# svd.net
KiCad netlist of a schematic drawn in EAGLE
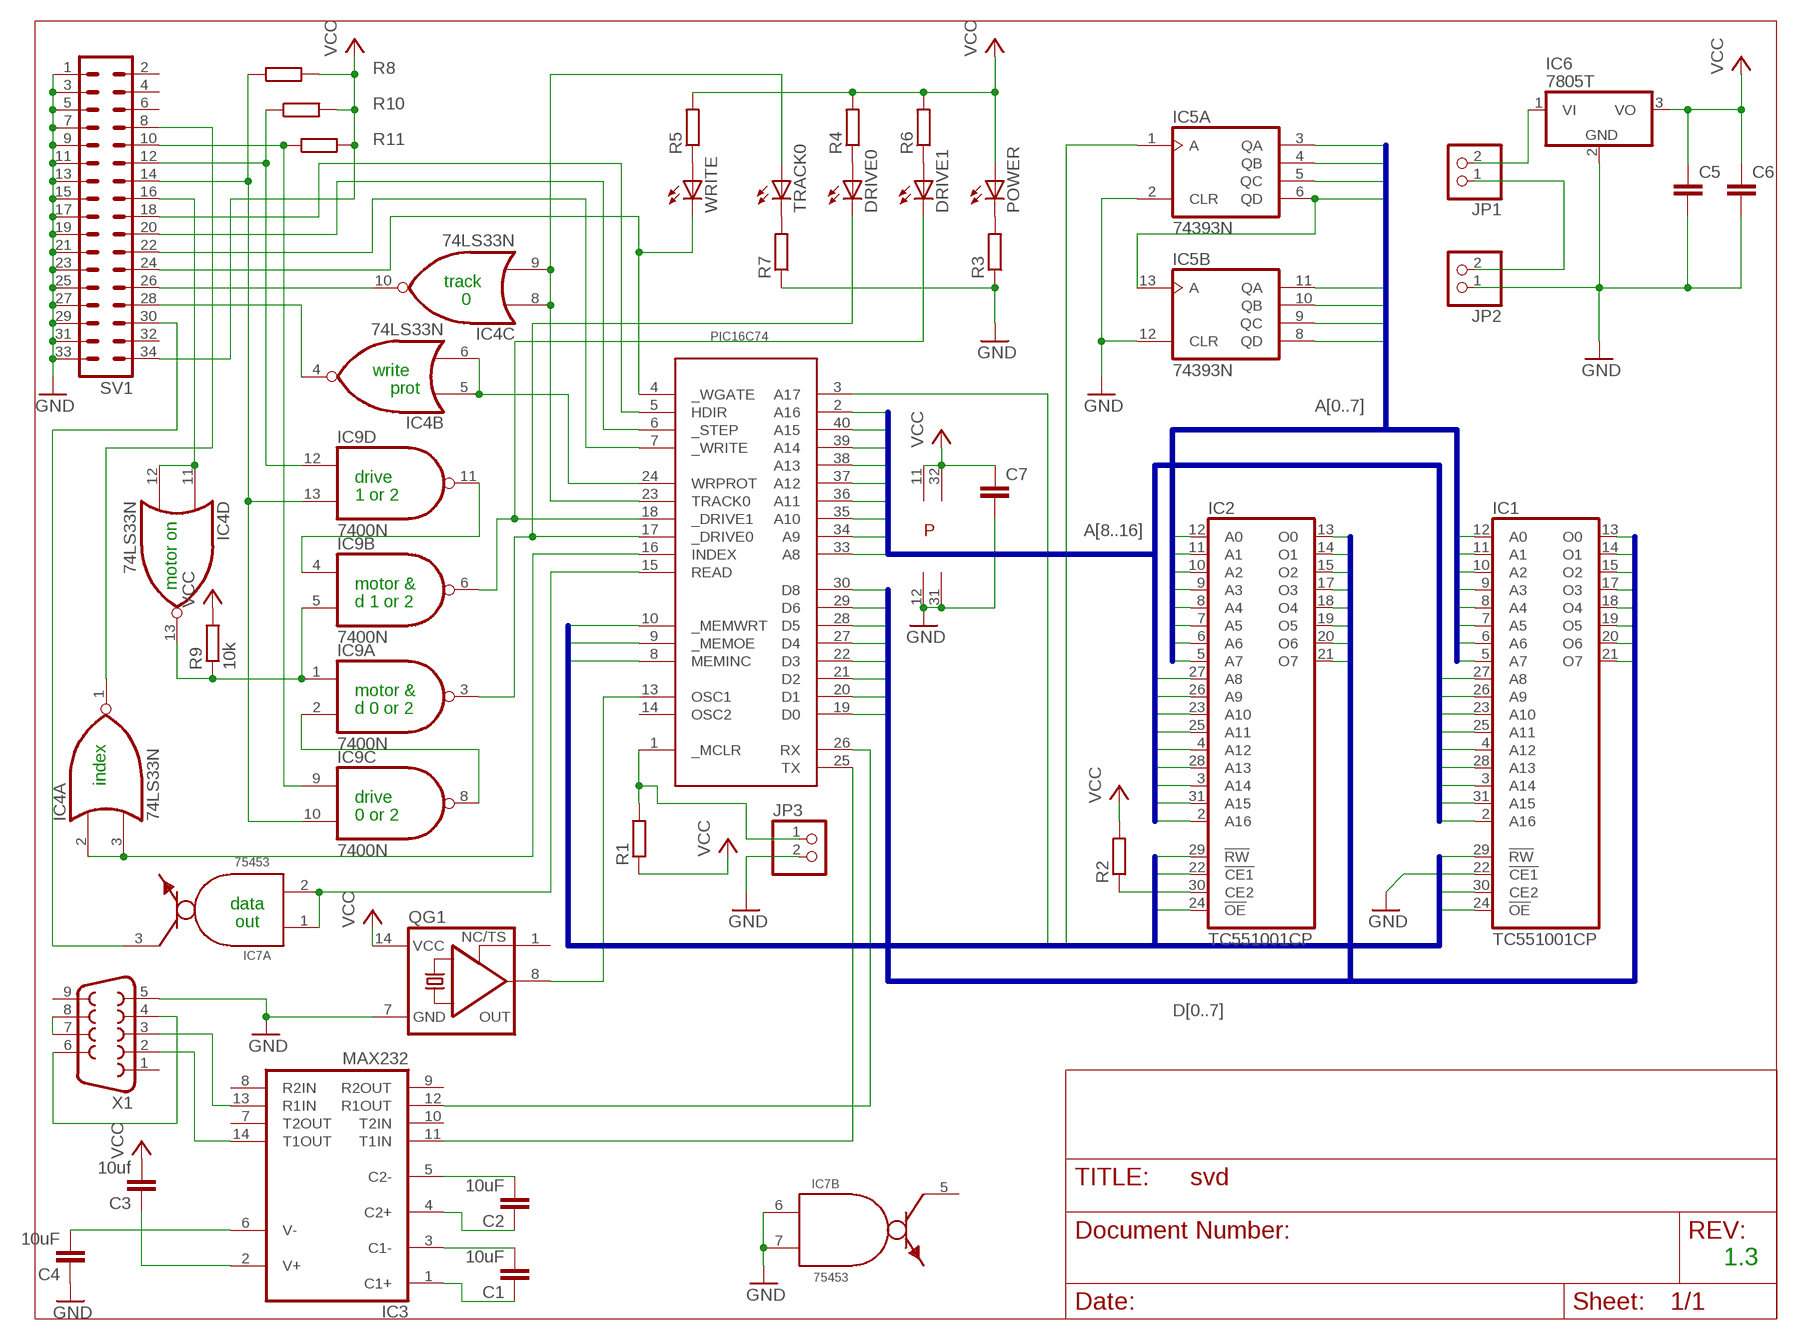
[diagram p0: schematic, sheet 1]

(export (version "E")
  (design (tool "Eeschema 10.0.6"))
  (components
    (comp (ref "C1")
      (value "10uF")
      (footprint "eagle-import:C2.5-5")
      (libsource (lib "eagle-import") (part "C2.5/5"))
    )
    (comp (ref "C2")
      (value "10uF")
      (footprint "eagle-import:C2.5-5")
      (libsource (lib "eagle-import") (part "C2.5/5"))
    )
    (comp (ref "C3")
      (value "10uf")
      (footprint "eagle-import:C2.5-5")
      (libsource (lib "eagle-import") (part "C2.5/5"))
    )
    (comp (ref "C4")
      (value "10uF")
      (footprint "eagle-import:C2.5-5")
      (libsource (lib "eagle-import") (part "C2.5/5"))
    )
    (comp (ref "C5")
      (value "C5/5")
      (footprint "eagle-import:C5B5")
      (libsource (lib "eagle-import") (part "C5/5"))
    )
    (comp (ref "C6")
      (value "C5/5")
      (footprint "eagle-import:C5B5")
      (libsource (lib "eagle-import") (part "C5/5"))
    )
    (comp (ref "C7")
      (value "C2,5-3")
      (footprint "eagle-import:C2.5-3")
      (libsource (lib "eagle-import") (part "C2,5-3"))
    )
    (comp (ref "DRIVE0")
      (value "LED3MM")
      (footprint "eagle-import:LED3MM")
      (libsource (lib "eagle-import") (part "LED3MM"))
    )
    (comp (ref "DRIVE1")
      (value "LED3MM")
      (footprint "eagle-import:LED3MM")
      (libsource (lib "eagle-import") (part "LED3MM"))
    )
    (comp (ref "IC1")
      (value "TC551001CP")
      (footprint "eagle-import:DIL32")
      (libsource (lib "eagle-import") (part "TC551001CP"))
    )
    (comp (ref "IC2")
      (value "TC551001CP")
      (footprint "eagle-import:DIL32")
      (libsource (lib "eagle-import") (part "TC551001CP"))
    )
    (comp (ref "IC3")
      (value "MAX232")
      (footprint "eagle-import:DIL16")
      (fields (field (name "MF") "MAXIM") (field (name "MPN") "MAX232ACPE+"))
      (libsource (lib "eagle-import") (part "MAX232"))
    )
    (comp (ref "IC4")
      (value "74LS33N")
      (footprint "eagle-import:DIL14")
      (libsource (lib "eagle-import") (part "7433NLS"))
    )
    (comp (ref "IC5")
      (value "74393N")
      (footprint "eagle-import:DIL14")
      (libsource (lib "eagle-import") (part "74393N"))
    )
    (comp (ref "IC6")
      (value "7805T")
      (footprint "eagle-import:TO220H")
      (libsource (lib "eagle-import") (part "78T05"))
    )
    (comp (ref "IC7")
      (value "75453")
      (footprint "eagle-import:DIL08")
      (libsource (lib "eagle-import") (part "75453"))
    )
    (comp (ref "IC9")
      (value "7400N")
      (footprint "eagle-import:DIL14")
      (libsource (lib "eagle-import") (part "7400N"))
    )
    (comp (ref "JP1")
      (value "PINHD-1X2")
      (footprint "eagle-import:1X02")
      (libsource (lib "eagle-import") (part "PINHD-1X2"))
    )
    (comp (ref "JP2")
      (value "PINHD-1X2")
      (footprint "eagle-import:1X02")
      (libsource (lib "eagle-import") (part "PINHD-1X2"))
    )
    (comp (ref "JP3")
      (value "PINHD-1X2")
      (footprint "eagle-import:1X02")
      (libsource (lib "eagle-import") (part "PINHD-1X2"))
    )
    (comp (ref "PIC16C74")
      (value "SVD-PIC16C74")
      (footprint "eagle-import:DIL40")
      (libsource (lib "eagle-import") (part "SVD-PIC16C74"))
    )
    (comp (ref "POWER")
      (value "LED3MM")
      (footprint "eagle-import:LED3MM")
      (libsource (lib "eagle-import") (part "LED3MM"))
    )
    (comp (ref "QG1")
      (value "XO-14")
      (footprint "eagle-import:DIL14S")
      (libsource (lib "eagle-import") (part "XO-14"))
    )
    (comp (ref "R1")
      (value "R-EU_0204/5")
      (footprint "eagle-import:0204_5")
      (libsource (lib "eagle-import") (part "R-EU_0204/5"))
    )
    (comp (ref "R2")
      (value "R-EU_0204/5")
      (footprint "eagle-import:0204_5")
      (libsource (lib "eagle-import") (part "R-EU_0204/5"))
    )
    (comp (ref "R3")
      (value "R-EU_0204/5")
      (footprint "eagle-import:0204_5")
      (libsource (lib "eagle-import") (part "R-EU_0204/5"))
    )
    (comp (ref "R4")
      (value "R-EU_0204/5")
      (footprint "eagle-import:0204_5")
      (libsource (lib "eagle-import") (part "R-EU_0204/5"))
    )
    (comp (ref "R5")
      (value "R-EU_0204/5")
      (footprint "eagle-import:0204_5")
      (libsource (lib "eagle-import") (part "R-EU_0204/5"))
    )
    (comp (ref "R6")
      (value "R-EU_0204/5")
      (footprint "eagle-import:0204_5")
      (libsource (lib "eagle-import") (part "R-EU_0204/5"))
    )
    (comp (ref "R7")
      (value "R-EU_0204/5")
      (footprint "eagle-import:0204_5")
      (libsource (lib "eagle-import") (part "R-EU_0204/5"))
    )
    (comp (ref "R8")
      (value "R-EU_0204/5")
      (footprint "eagle-import:0204_5")
      (libsource (lib "eagle-import") (part "R-EU_0204/5"))
    )
    (comp (ref "R9")
      (value "10k")
      (footprint "eagle-import:0204_5")
      (libsource (lib "eagle-import") (part "R-EU_0204/5"))
    )
    (comp (ref "R10")
      (value "R-EU_0204/5")
      (footprint "eagle-import:0204_5")
      (libsource (lib "eagle-import") (part "R-EU_0204/5"))
    )
    (comp (ref "R11")
      (value "R-EU_0204/5")
      (footprint "eagle-import:0204_5")
      (libsource (lib "eagle-import") (part "R-EU_0204/5"))
    )
    (comp (ref "SV1")
      (value "ML34")
      (footprint "eagle-import:ML34")
      (libsource (lib "eagle-import") (part "ML34"))
    )
    (comp (ref "TRACK0")
      (value "LED3MM")
      (footprint "eagle-import:LED3MM")
      (libsource (lib "eagle-import") (part "LED3MM"))
    )
    (comp (ref "WRITE")
      (value "LED3MM")
      (footprint "eagle-import:LED3MM")
      (libsource (lib "eagle-import") (part "LED3MM"))
    )
    (comp (ref "X1")
      (value "F09HP")
      (footprint "eagle-import:F09HP")
      (libsource (lib "eagle-import") (part "F09HP"))
    )
  )
  (nets
    (net (code "1") (name "/A0") (class "Default")
      (node (ref "IC1") (pin "12") (pinfunction "A0_12") (pintype "input"))
      (node (ref "IC2") (pin "12") (pinfunction "A0_12") (pintype "input"))
      (node (ref "IC5") (pin "3") (pinfunction "QA_3") (pintype "output"))
    )
    (net (code "2") (name "/A1") (class "Default")
      (node (ref "IC1") (pin "11") (pinfunction "A1_11") (pintype "input"))
      (node (ref "IC2") (pin "11") (pinfunction "A1_11") (pintype "input"))
      (node (ref "IC5") (pin "4") (pinfunction "QB_4") (pintype "output"))
    )
    (net (code "3") (name "/A2") (class "Default")
      (node (ref "IC1") (pin "10") (pinfunction "A2_10") (pintype "input"))
      (node (ref "IC2") (pin "10") (pinfunction "A2_10") (pintype "input"))
      (node (ref "IC5") (pin "5") (pinfunction "QC_5") (pintype "output"))
    )
    (net (code "4") (name "/A3") (class "Default")
      (node (ref "IC1") (pin "9") (pinfunction "A3_9") (pintype "input"))
      (node (ref "IC2") (pin "9") (pinfunction "A3_9") (pintype "input"))
      (node (ref "IC5") (pin "13") (pinfunction "A_13") (pintype "input"))
      (node (ref "IC5") (pin "6") (pinfunction "QD_6") (pintype "output"))
    )
    (net (code "5") (name "/A4") (class "Default")
      (node (ref "IC1") (pin "8") (pinfunction "A4_8") (pintype "input"))
      (node (ref "IC2") (pin "8") (pinfunction "A4_8") (pintype "input"))
      (node (ref "IC5") (pin "11") (pinfunction "QA_11") (pintype "output"))
    )
    (net (code "6") (name "/A5") (class "Default")
      (node (ref "IC1") (pin "7") (pinfunction "A5_7") (pintype "input"))
      (node (ref "IC2") (pin "7") (pinfunction "A5_7") (pintype "input"))
      (node (ref "IC5") (pin "10") (pinfunction "QB_10") (pintype "output"))
    )
    (net (code "7") (name "/A6") (class "Default")
      (node (ref "IC1") (pin "6") (pinfunction "A6_6") (pintype "input"))
      (node (ref "IC2") (pin "6") (pinfunction "A6_6") (pintype "input"))
      (node (ref "IC5") (pin "9") (pinfunction "QC_9") (pintype "output"))
    )
    (net (code "8") (name "/A7") (class "Default")
      (node (ref "IC1") (pin "5") (pinfunction "A7_5") (pintype "input"))
      (node (ref "IC2") (pin "5") (pinfunction "A7_5") (pintype "input"))
      (node (ref "IC5") (pin "8") (pinfunction "QD_8") (pintype "output"))
    )
    (net (code "9") (name "/A8") (class "Default")
      (node (ref "IC1") (pin "27") (pinfunction "A8_27") (pintype "input"))
      (node (ref "IC2") (pin "27") (pinfunction "A8_27") (pintype "input"))
      (node (ref "PIC16C74") (pin "33") (pinfunction "A8_33") (pintype "output"))
    )
    (net (code "10") (name "/A9") (class "Default")
      (node (ref "IC1") (pin "26") (pinfunction "A9_26") (pintype "input"))
      (node (ref "IC2") (pin "26") (pinfunction "A9_26") (pintype "input"))
      (node (ref "PIC16C74") (pin "34") (pinfunction "A9_34") (pintype "output"))
    )
    (net (code "11") (name "/A10") (class "Default")
      (node (ref "IC1") (pin "23") (pinfunction "A10_23") (pintype "input"))
      (node (ref "IC2") (pin "23") (pinfunction "A10_23") (pintype "input"))
      (node (ref "PIC16C74") (pin "35") (pinfunction "A10_35") (pintype "output"))
    )
    (net (code "12") (name "/A11") (class "Default")
      (node (ref "IC1") (pin "25") (pinfunction "A11_25") (pintype "input"))
      (node (ref "IC2") (pin "25") (pinfunction "A11_25") (pintype "input"))
      (node (ref "PIC16C74") (pin "36") (pinfunction "A11_36") (pintype "output"))
    )
    (net (code "13") (name "/A12") (class "Default")
      (node (ref "IC1") (pin "4") (pinfunction "A12_4") (pintype "input"))
      (node (ref "IC2") (pin "4") (pinfunction "A12_4") (pintype "input"))
      (node (ref "PIC16C74") (pin "37") (pinfunction "A12_37") (pintype "output"))
    )
    (net (code "14") (name "/A13") (class "Default")
      (node (ref "IC1") (pin "28") (pinfunction "A13_28") (pintype "input"))
      (node (ref "IC2") (pin "28") (pinfunction "A13_28") (pintype "input"))
      (node (ref "PIC16C74") (pin "38") (pinfunction "A13_38") (pintype "output"))
    )
    (net (code "15") (name "/A14") (class "Default")
      (node (ref "IC1") (pin "3") (pinfunction "A14_3") (pintype "input"))
      (node (ref "IC2") (pin "3") (pinfunction "A14_3") (pintype "input"))
      (node (ref "PIC16C74") (pin "39") (pinfunction "A14_39") (pintype "output"))
    )
    (net (code "16") (name "/A15") (class "Default")
      (node (ref "IC1") (pin "31") (pinfunction "A15_31") (pintype "input"))
      (node (ref "IC2") (pin "31") (pinfunction "A15_31") (pintype "input"))
      (node (ref "PIC16C74") (pin "40") (pinfunction "A15_40") (pintype "output"))
    )
    (net (code "17") (name "/A16") (class "Default")
      (node (ref "IC1") (pin "2") (pinfunction "A16_2") (pintype "input"))
      (node (ref "IC2") (pin "2") (pinfunction "A16_2") (pintype "input"))
      (node (ref "PIC16C74") (pin "2") (pinfunction "A16_2") (pintype "output"))
    )
    (net (code "18") (name "/A17") (class "Default")
      (node (ref "IC1") (pin "30") (pinfunction "CE2_30") (pintype "input"))
      (node (ref "IC2") (pin "22") (pinfunction "~{CE1}_22") (pintype "input"))
      (node (ref "PIC16C74") (pin "3") (pinfunction "A17_3") (pintype "output"))
    )
    (net (code "21") (name "/CLK") (class "Default")
      (node (ref "IC5") (pin "1") (pinfunction "A_1") (pintype "input"))
      (node (ref "PIC16C74") (pin "8") (pinfunction "MEMINC_8") (pintype "output"))
    )
    (net (code "22") (name "/D0") (class "Default")
      (node (ref "IC1") (pin "13") (pinfunction "O0_13") (pintype "tri_state"))
      (node (ref "IC2") (pin "13") (pinfunction "O0_13") (pintype "tri_state"))
      (node (ref "PIC16C74") (pin "19") (pinfunction "D0_19") (pintype "bidirectional"))
    )
    (net (code "23") (name "/D1") (class "Default")
      (node (ref "IC1") (pin "14") (pinfunction "O1_14") (pintype "tri_state"))
      (node (ref "IC2") (pin "14") (pinfunction "O1_14") (pintype "tri_state"))
      (node (ref "PIC16C74") (pin "20") (pinfunction "D1_20") (pintype "bidirectional"))
    )
    (net (code "24") (name "/D2") (class "Default")
      (node (ref "IC1") (pin "15") (pinfunction "O2_15") (pintype "tri_state"))
      (node (ref "IC2") (pin "15") (pinfunction "O2_15") (pintype "tri_state"))
      (node (ref "PIC16C74") (pin "21") (pinfunction "D2_21") (pintype "bidirectional"))
    )
    (net (code "25") (name "/D3") (class "Default")
      (node (ref "IC1") (pin "17") (pinfunction "O3_17") (pintype "tri_state"))
      (node (ref "IC2") (pin "17") (pinfunction "O3_17") (pintype "tri_state"))
      (node (ref "PIC16C74") (pin "22") (pinfunction "D3_22") (pintype "bidirectional"))
    )
    (net (code "26") (name "/D4") (class "Default")
      (node (ref "IC1") (pin "18") (pinfunction "O4_18") (pintype "tri_state"))
      (node (ref "IC2") (pin "18") (pinfunction "O4_18") (pintype "tri_state"))
      (node (ref "PIC16C74") (pin "27") (pinfunction "D4_27") (pintype "bidirectional"))
    )
    (net (code "27") (name "/D5") (class "Default")
      (node (ref "IC1") (pin "19") (pinfunction "O5_19") (pintype "tri_state"))
      (node (ref "IC2") (pin "19") (pinfunction "O5_19") (pintype "tri_state"))
      (node (ref "PIC16C74") (pin "28") (pinfunction "D5_28") (pintype "bidirectional"))
    )
    (net (code "28") (name "/D6") (class "Default")
      (node (ref "IC1") (pin "20") (pinfunction "O6_20") (pintype "tri_state"))
      (node (ref "IC2") (pin "20") (pinfunction "O6_20") (pintype "tri_state"))
      (node (ref "PIC16C74") (pin "29") (pinfunction "D6_29") (pintype "bidirectional"))
    )
    (net (code "29") (name "/D7") (class "Default")
      (node (ref "IC1") (pin "21") (pinfunction "O7_21") (pintype "tri_state"))
      (node (ref "IC2") (pin "21") (pinfunction "O7_21") (pintype "tri_state"))
      (node (ref "PIC16C74") (pin "30") (pinfunction "D8_30") (pintype "bidirectional"))
    )
    (net (code "31") (name "/~{OE}") (class "Default")
      (node (ref "IC1") (pin "24") (pinfunction "~{OE}_24") (pintype "input"))
      (node (ref "IC2") (pin "24") (pinfunction "~{OE}_24") (pintype "input"))
      (node (ref "PIC16C74") (pin "9") (pinfunction "_MEMOE_9") (pintype "output"))
    )
    (net (code "32") (name "/~{WE}") (class "Default")
      (node (ref "IC1") (pin "29") (pinfunction "~{RW}_29") (pintype "input"))
      (node (ref "IC2") (pin "29") (pinfunction "~{RW}_29") (pintype "input"))
      (node (ref "PIC16C74") (pin "10") (pinfunction "_MEMWRT_10") (pintype "output"))
    )
    (net (code "33") (name "GND") (class "Default")
      (node (ref "C4") (pin "1") (pinfunction "1_1") (pintype "passive"))
      (node (ref "C5") (pin "2") (pinfunction "2_2") (pintype "passive"))
      (node (ref "C6") (pin "2") (pinfunction "2_2") (pintype "passive"))
      (node (ref "C7") (pin "2") (pinfunction "2_2") (pintype "passive"))
      (node (ref "IC1") (pin "22") (pinfunction "~{CE1}_22") (pintype "input"))
      (node (ref "IC5") (pin "12") (pinfunction "CLR_12") (pintype "input"))
      (node (ref "IC5") (pin "2") (pinfunction "CLR_2") (pintype "input"))
      (node (ref "IC6") (pin "2") (pinfunction "GND_2") (pintype "passive"))
      (node (ref "IC7") (pin "6") (pinfunction "I0_6") (pintype "input"))
      (node (ref "IC7") (pin "7") (pinfunction "I1_7") (pintype "input"))
      (node (ref "JP2") (pin "1") (pinfunction "1_1") (pintype "passive"))
      (node (ref "JP3") (pin "2") (pinfunction "2_2") (pintype "passive"))
      (node (ref "PIC16C74") (pin "12") (pinfunction "GND_12") (pintype "power_in"))
      (node (ref "PIC16C74") (pin "31") (pinfunction "GND_31") (pintype "power_in"))
      (node (ref "QG1") (pin "7") (pinfunction "GND_7") (pintype "power_in"))
      (node (ref "R3") (pin "1") (pinfunction "1_1") (pintype "passive"))
      (node (ref "R7") (pin "1") (pinfunction "1_1") (pintype "passive"))
      (node (ref "SV1") (pin "1") (pinfunction "1_1") (pintype "passive"))
      (node (ref "SV1") (pin "11") (pinfunction "11_11") (pintype "passive"))
      (node (ref "SV1") (pin "13") (pinfunction "13_13") (pintype "passive"))
      (node (ref "SV1") (pin "15") (pinfunction "15_15") (pintype "passive"))
      (node (ref "SV1") (pin "17") (pinfunction "17_17") (pintype "passive"))
      (node (ref "SV1") (pin "19") (pinfunction "19_19") (pintype "passive"))
      (node (ref "SV1") (pin "21") (pinfunction "21_21") (pintype "passive"))
      (node (ref "SV1") (pin "23") (pinfunction "23_23") (pintype "passive"))
      (node (ref "SV1") (pin "25") (pinfunction "25_25") (pintype "passive"))
      (node (ref "SV1") (pin "27") (pinfunction "27_27") (pintype "passive"))
      (node (ref "SV1") (pin "29") (pinfunction "29_29") (pintype "passive"))
      (node (ref "SV1") (pin "3") (pinfunction "3_3") (pintype "passive"))
      (node (ref "SV1") (pin "31") (pinfunction "31_31") (pintype "passive"))
      (node (ref "SV1") (pin "33") (pinfunction "33_33") (pintype "passive"))
      (node (ref "SV1") (pin "5") (pinfunction "5_5") (pintype "passive"))
      (node (ref "SV1") (pin "7") (pinfunction "7_7") (pintype "passive"))
      (node (ref "SV1") (pin "9") (pinfunction "9_9") (pintype "passive"))
      (node (ref "X1") (pin "5") (pinfunction "5_5") (pintype "passive"))
    )
    (net (code "34") (name "Net-(DRIVE0-C)") (class "Default")
      (node (ref "DRIVE0") (pin "K") (pinfunction "C_K") (pintype "passive"))
      (node (ref "IC9") (pin "3") (pinfunction "O_3") (pintype "output"))
      (node (ref "PIC16C74") (pin "17") (pinfunction "_DRIVE0_17") (pintype "input"))
    )
    (net (code "35") (name "Net-(DRIVE0-PadA)") (class "Default")
      (node (ref "DRIVE0") (pin "A") (pinfunction "A_A") (pintype "passive"))
      (node (ref "R4") (pin "1") (pinfunction "1_1") (pintype "passive"))
    )
    (net (code "36") (name "Net-(DRIVE1-C)") (class "Default")
      (node (ref "DRIVE1") (pin "K") (pinfunction "C_K") (pintype "passive"))
      (node (ref "IC9") (pin "6") (pinfunction "O_6") (pintype "output"))
      (node (ref "PIC16C74") (pin "18") (pinfunction "_DRIVE1_18") (pintype "input"))
    )
    (net (code "37") (name "Net-(DRIVE1-PadA)") (class "Default")
      (node (ref "DRIVE1") (pin "A") (pinfunction "A_A") (pintype "passive"))
      (node (ref "R6") (pin "1") (pinfunction "1_1") (pintype "passive"))
    )
    (net (code "38") (name "Net-(IC2B-CE2)") (class "Default")
      (node (ref "IC2") (pin "30") (pinfunction "CE2_30") (pintype "input"))
      (node (ref "R2") (pin "1") (pinfunction "1_1") (pintype "passive"))
    )
    (net (code "39") (name "Net-(IC3A-C1+)") (class "Default")
      (node (ref "C1") (pin "1") (pinfunction "1_1") (pintype "passive"))
      (node (ref "IC3") (pin "1") (pinfunction "C1+_1") (pintype "bidirectional"))
    )
    (net (code "40") (name "Net-(IC3A-C1-)") (class "Default")
      (node (ref "C1") (pin "2") (pinfunction "2_2") (pintype "passive"))
      (node (ref "IC3") (pin "3") (pinfunction "C1-_3") (pintype "bidirectional"))
    )
    (net (code "41") (name "Net-(IC3A-C2+)") (class "Default")
      (node (ref "C2") (pin "1") (pinfunction "1_1") (pintype "passive"))
      (node (ref "IC3") (pin "4") (pinfunction "C2+_4") (pintype "bidirectional"))
    )
    (net (code "42") (name "Net-(IC3A-C2-)") (class "Default")
      (node (ref "C2") (pin "2") (pinfunction "2_2") (pintype "passive"))
      (node (ref "IC3") (pin "5") (pinfunction "C2-_5") (pintype "bidirectional"))
    )
    (net (code "43") (name "Net-(IC3A-R1IN)") (class "Default")
      (node (ref "IC3") (pin "13") (pinfunction "R1IN_13") (pintype "input"))
      (node (ref "X1") (pin "3") (pinfunction "3_3") (pintype "passive"))
    )
    (net (code "44") (name "Net-(IC3A-R1OUT)") (class "Default")
      (node (ref "IC3") (pin "12") (pinfunction "R1OUT_12") (pintype "output"))
      (node (ref "PIC16C74") (pin "26") (pinfunction "RX_26") (pintype "input"))
    )
    (net (code "45") (name "Net-(IC3A-T1IN)") (class "Default")
      (node (ref "IC3") (pin "11") (pinfunction "T1IN_11") (pintype "input"))
      (node (ref "PIC16C74") (pin "25") (pinfunction "TX_25") (pintype "output"))
    )
    (net (code "46") (name "Net-(IC3A-T1OUT)") (class "Default")
      (node (ref "IC3") (pin "14") (pinfunction "T1OUT_14") (pintype "output"))
      (node (ref "X1") (pin "2") (pinfunction "2_2") (pintype "passive"))
    )
    (net (code "47") (name "Net-(IC3A-V+)") (class "Default")
      (node (ref "C3") (pin "1") (pinfunction "1_1") (pintype "passive"))
      (node (ref "IC3") (pin "2") (pinfunction "V+_2") (pintype "bidirectional"))
    )
    (net (code "48") (name "Net-(IC3A-V-)") (class "Default")
      (node (ref "C4") (pin "2") (pinfunction "2_2") (pintype "passive"))
      (node (ref "IC3") (pin "6") (pinfunction "V-_6") (pintype "bidirectional"))
    )
    (net (code "49") (name "Net-(IC4A-I0)") (class "Default")
      (node (ref "IC4") (pin "2") (pinfunction "I0_2") (pintype "input"))
      (node (ref "IC4") (pin "3") (pinfunction "I1_3") (pintype "input"))
      (node (ref "PIC16C74") (pin "16") (pinfunction "INDEX_16") (pintype "output"))
    )
    (net (code "50") (name "Net-(IC4A-O)") (class "Default")
      (node (ref "IC4") (pin "1") (pinfunction "O_1") (pintype "output"))
      (node (ref "SV1") (pin "8") (pinfunction "8_8") (pintype "passive"))
    )
    (net (code "51") (name "Net-(IC4B-I0)") (class "Default")
      (node (ref "IC4") (pin "5") (pinfunction "I0_5") (pintype "input"))
      (node (ref "IC4") (pin "6") (pinfunction "I1_6") (pintype "input"))
      (node (ref "PIC16C74") (pin "24") (pinfunction "WRPROT_24") (pintype "output"))
    )
    (net (code "52") (name "Net-(IC4B-O)") (class "Default")
      (node (ref "IC4") (pin "4") (pinfunction "O_4") (pintype "output"))
      (node (ref "SV1") (pin "28") (pinfunction "28_28") (pintype "passive"))
    )
    (net (code "53") (name "Net-(IC4C-I0)") (class "Default")
      (node (ref "IC4") (pin "8") (pinfunction "I0_8") (pintype "input"))
      (node (ref "IC4") (pin "9") (pinfunction "I1_9") (pintype "input"))
      (node (ref "PIC16C74") (pin "23") (pinfunction "TRACK0_23") (pintype "output"))
      (node (ref "TRACK0") (pin "A") (pinfunction "A_A") (pintype "passive"))
    )
    (net (code "54") (name "Net-(IC4C-O)") (class "Default")
      (node (ref "IC4") (pin "10") (pinfunction "O_10") (pintype "output"))
      (node (ref "SV1") (pin "26") (pinfunction "26_26") (pintype "passive"))
    )
    (net (code "55") (name "Net-(IC4D-I0)") (class "Default")
      (node (ref "IC4") (pin "11") (pinfunction "I0_11") (pintype "input"))
      (node (ref "IC4") (pin "12") (pinfunction "I1_12") (pintype "input"))
      (node (ref "SV1") (pin "16") (pinfunction "16_16") (pintype "passive"))
    )
    (net (code "56") (name "Net-(IC4D-O)") (class "Default")
      (node (ref "IC4") (pin "13") (pinfunction "O_13") (pintype "output"))
      (node (ref "IC9") (pin "1") (pinfunction "I0_1") (pintype "input"))
      (node (ref "IC9") (pin "5") (pinfunction "I1_5") (pintype "input"))
      (node (ref "R9") (pin "1") (pinfunction "1_1") (pintype "passive"))
    )
    (net (code "57") (name "Net-(IC6-VI)") (class "Default")
      (node (ref "IC6") (pin "1") (pinfunction "VI_1") (pintype "input"))
      (node (ref "JP1") (pin "2") (pinfunction "2_2") (pintype "passive"))
    )
    (net (code "58") (name "Net-(IC7A-I0)") (class "Default")
      (node (ref "IC7") (pin "1") (pinfunction "I0_1") (pintype "input"))
      (node (ref "IC7") (pin "2") (pinfunction "I1_2") (pintype "input"))
      (node (ref "PIC16C74") (pin "15") (pinfunction "READ_15") (pintype "output"))
    )
    (net (code "59") (name "Net-(IC7A-O)") (class "Default")
      (node (ref "IC7") (pin "3") (pinfunction "O_3") (pintype "output"))
      (node (ref "SV1") (pin "30") (pinfunction "30_30") (pintype "passive"))
    )
    (net (code "60") (name "Net-(IC9A-I1)") (class "Default")
      (node (ref "IC9") (pin "2") (pinfunction "I1_2") (pintype "input"))
      (node (ref "IC9") (pin "8") (pinfunction "O_8") (pintype "output"))
    )
    (net (code "61") (name "Net-(IC9B-I0)") (class "Default")
      (node (ref "IC9") (pin "11") (pinfunction "O_11") (pintype "output"))
      (node (ref "IC9") (pin "4") (pinfunction "I0_4") (pintype "input"))
    )
    (net (code "62") (name "Net-(IC9C-I0)") (class "Default")
      (node (ref "IC9") (pin "9") (pinfunction "I0_9") (pintype "input"))
      (node (ref "R11") (pin "1") (pinfunction "1_1") (pintype "passive"))
      (node (ref "SV1") (pin "10") (pinfunction "10_10") (pintype "passive"))
    )
    (net (code "63") (name "Net-(IC9C-I1)") (class "Default")
      (node (ref "IC9") (pin "10") (pinfunction "I1_10") (pintype "input"))
      (node (ref "IC9") (pin "13") (pinfunction "I1_13") (pintype "input"))
      (node (ref "R8") (pin "1") (pinfunction "1_1") (pintype "passive"))
      (node (ref "SV1") (pin "14") (pinfunction "14_14") (pintype "passive"))
    )
    (net (code "64") (name "Net-(IC9D-I0)") (class "Default")
      (node (ref "IC9") (pin "12") (pinfunction "I0_12") (pintype "input"))
      (node (ref "R10") (pin "1") (pinfunction "1_1") (pintype "passive"))
      (node (ref "SV1") (pin "12") (pinfunction "12_12") (pintype "passive"))
    )
    (net (code "65") (name "Net-(JP1-Pad1)") (class "Default")
      (node (ref "JP1") (pin "1") (pinfunction "1_1") (pintype "passive"))
      (node (ref "JP2") (pin "2") (pinfunction "2_2") (pintype "passive"))
    )
    (net (code "66") (name "Net-(PIC16C74-HDIR)") (class "Default")
      (node (ref "PIC16C74") (pin "5") (pinfunction "HDIR_5") (pintype "input"))
      (node (ref "SV1") (pin "18") (pinfunction "18_18") (pintype "passive"))
    )
    (net (code "67") (name "Net-(PIC16C74-OSC1)") (class "Default")
      (node (ref "PIC16C74") (pin "13") (pinfunction "OSC1_13") (pintype "input"))
      (node (ref "QG1") (pin "8") (pinfunction "OUT_8") (pintype "output"))
    )
    (net (code "68") (name "Net-(PIC16C74-_MCLR)") (class "Default")
      (node (ref "JP3") (pin "1") (pinfunction "1_1") (pintype "passive"))
      (node (ref "PIC16C74") (pin "1") (pinfunction "_MCLR_1") (pintype "input"))
      (node (ref "R1") (pin "2") (pinfunction "2_2") (pintype "passive"))
    )
    (net (code "69") (name "Net-(PIC16C74-_STEP)") (class "Default")
      (node (ref "PIC16C74") (pin "6") (pinfunction "_STEP_6") (pintype "input"))
      (node (ref "SV1") (pin "20") (pinfunction "20_20") (pintype "passive"))
    )
    (net (code "70") (name "Net-(PIC16C74-_WGATE)") (class "Default")
      (node (ref "PIC16C74") (pin "4") (pinfunction "_WGATE_4") (pintype "input"))
      (node (ref "SV1") (pin "24") (pinfunction "24_24") (pintype "passive"))
      (node (ref "WRITE") (pin "K") (pinfunction "C_K") (pintype "passive"))
    )
    (net (code "71") (name "Net-(PIC16C74-_WRITE)") (class "Default")
      (node (ref "PIC16C74") (pin "7") (pinfunction "_WRITE_7") (pintype "input"))
      (node (ref "SV1") (pin "22") (pinfunction "22_22") (pintype "passive"))
    )
    (net (code "72") (name "Net-(POWER-C)") (class "Default")
      (node (ref "POWER") (pin "K") (pinfunction "C_K") (pintype "passive"))
      (node (ref "R3") (pin "2") (pinfunction "2_2") (pintype "passive"))
    )
    (net (code "73") (name "Net-(R5-Pad1)") (class "Default")
      (node (ref "R5") (pin "1") (pinfunction "1_1") (pintype "passive"))
      (node (ref "WRITE") (pin "A") (pinfunction "A_A") (pintype "passive"))
    )
    (net (code "74") (name "Net-(TRACK0-C)") (class "Default")
      (node (ref "R7") (pin "2") (pinfunction "2_2") (pintype "passive"))
      (node (ref "TRACK0") (pin "K") (pinfunction "C_K") (pintype "passive"))
    )
    (net (code "75") (name "Net-(X1-Pad4)") (class "Default")
      (node (ref "X1") (pin "4") (pinfunction "4_4") (pintype "passive"))
      (node (ref "X1") (pin "6") (pinfunction "6_6") (pintype "passive"))
    )
    (net (code "76") (name "Net-(X1-Pad7)") (class "Default")
      (node (ref "X1") (pin "7") (pinfunction "7_7") (pintype "passive"))
      (node (ref "X1") (pin "8") (pinfunction "8_8") (pintype "passive"))
    )
    (net (code "77") (name "VCC") (class "Default")
      (node (ref "C3") (pin "2") (pinfunction "2_2") (pintype "passive"))
      (node (ref "C5") (pin "1") (pinfunction "1_1") (pintype "passive"))
      (node (ref "C6") (pin "1") (pinfunction "1_1") (pintype "passive"))
      (node (ref "C7") (pin "1") (pinfunction "1_1") (pintype "passive"))
      (node (ref "IC6") (pin "3") (pinfunction "VO_3") (pintype "passive"))
      (node (ref "PIC16C74") (pin "11") (pinfunction "VCC_11") (pintype "power_in"))
      (node (ref "PIC16C74") (pin "32") (pinfunction "VCC_32") (pintype "power_in"))
      (node (ref "POWER") (pin "A") (pinfunction "A_A") (pintype "passive"))
      (node (ref "QG1") (pin "14") (pinfunction "VCC_14") (pintype "power_in"))
      (node (ref "R1") (pin "1") (pinfunction "1_1") (pintype "passive"))
      (node (ref "R10") (pin "2") (pinfunction "2_2") (pintype "passive"))
      (node (ref "R11") (pin "2") (pinfunction "2_2") (pintype "passive"))
      (node (ref "R2") (pin "2") (pinfunction "2_2") (pintype "passive"))
      (node (ref "R4") (pin "2") (pinfunction "2_2") (pintype "passive"))
      (node (ref "R5") (pin "2") (pinfunction "2_2") (pintype "passive"))
      (node (ref "R6") (pin "2") (pinfunction "2_2") (pintype "passive"))
      (node (ref "R8") (pin "2") (pinfunction "2_2") (pintype "passive"))
      (node (ref "R9") (pin "2") (pinfunction "2_2") (pintype "passive"))
      (node (ref "SV1") (pin "34") (pinfunction "34_34") (pintype "passive"))
    )
    (net (code "78") (name "unconnected-(IC3A-R2IN-Pad8)") (class "Default")
      (node (ref "IC3") (pin "8") (pinfunction "R2IN_8") (pintype "input"))
    )
    (net (code "79") (name "unconnected-(IC3A-R2OUT-Pad9)") (class "Default")
      (node (ref "IC3") (pin "9") (pinfunction "R2OUT_9") (pintype "output"))
    )
    (net (code "80") (name "unconnected-(IC3A-T2IN-Pad10)") (class "Default")
      (node (ref "IC3") (pin "10") (pinfunction "T2IN_10") (pintype "input"))
    )
    (net (code "81") (name "unconnected-(IC3A-T2OUT-Pad7)") (class "Default")
      (node (ref "IC3") (pin "7") (pinfunction "T2OUT_7") (pintype "output"))
    )
    (net (code "82") (name "unconnected-(IC7B-O-Pad5)") (class "Default")
      (node (ref "IC7") (pin "5") (pinfunction "O_5") (pintype "output"))
    )
    (net (code "83") (name "unconnected-(PIC16C74-OSC2-Pad14)") (class "Default")
      (node (ref "PIC16C74") (pin "14") (pinfunction "OSC2_14") (pintype "input"))
    )
    (net (code "84") (name "unconnected-(QG1-TS-Pad1)") (class "Default")
      (node (ref "QG1") (pin "1") (pinfunction "TS_1") (pintype "passive"))
    )
    (net (code "85") (name "unconnected-(SV1-Pad2)") (class "Default")
      (node (ref "SV1") (pin "2") (pinfunction "2_2") (pintype "passive"))
    )
    (net (code "86") (name "unconnected-(SV1-Pad4)") (class "Default")
      (node (ref "SV1") (pin "4") (pinfunction "4_4") (pintype "passive"))
    )
    (net (code "87") (name "unconnected-(SV1-Pad6)") (class "Default")
      (node (ref "SV1") (pin "6") (pinfunction "6_6") (pintype "passive"))
    )
    (net (code "88") (name "unconnected-(SV1-Pad32)") (class "Default")
      (node (ref "SV1") (pin "32") (pinfunction "32_32") (pintype "passive"))
    )
    (net (code "89") (name "unconnected-(X1-Pad1)") (class "Default")
      (node (ref "X1") (pin "1") (pinfunction "1_1") (pintype "passive"))
    )
    (net (code "90") (name "unconnected-(X1-Pad9)") (class "Default")
      (node (ref "X1") (pin "9") (pinfunction "9_9") (pintype "passive"))
    )
  )
)
